# FuenteProto_v11.net
KiCad netlist of a schematic drawn in EAGLE
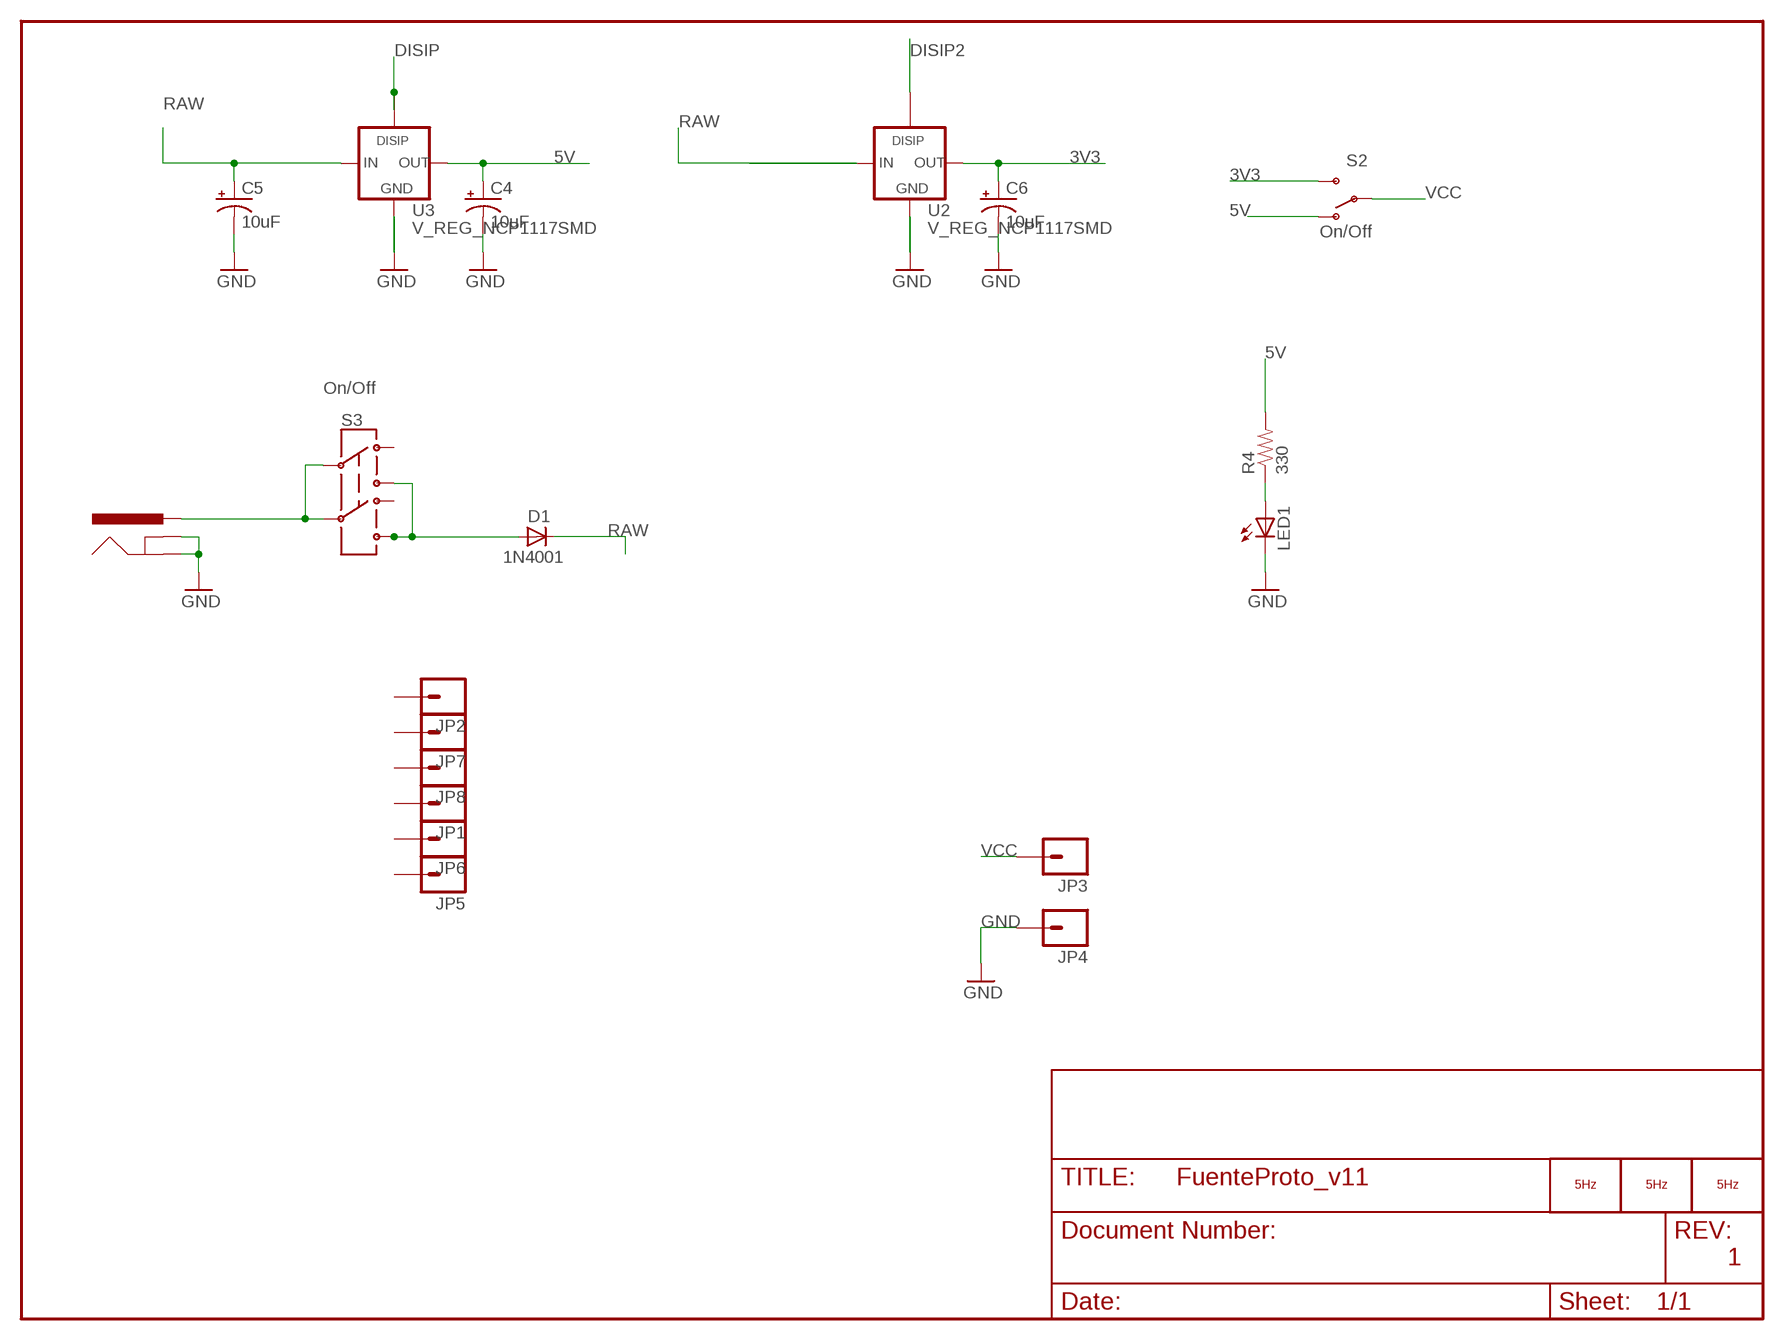
[diagram p0: schematic, sheet 1]

(export (version "E")
  (design (tool "Eeschema 10.0.6"))
  (components
    (comp (ref "C4")
      (value "10uF")
      (footprint "eagle-import:EIA3216")
      (libsource (lib "eagle-import") (part "CAP_POL1206"))
    )
    (comp (ref "C5")
      (value "10uF")
      (footprint "eagle-import:EIA3216")
      (libsource (lib "eagle-import") (part "CAP_POL1206"))
    )
    (comp (ref "C6")
      (value "10uF")
      (footprint "eagle-import:EIA3216")
      (libsource (lib "eagle-import") (part "CAP_POL1206"))
    )
    (comp (ref "D1")
      (value "1N4001")
      (footprint "eagle-import:SMA-DIODE")
      (libsource (lib "eagle-import") (part "DIODESMA"))
    )
    (comp (ref "J1")
      (value "POWER_JACKPTH")
      (footprint "eagle-import:POWER_JACK_PTH")
      (libsource (lib "eagle-import") (part "POWER_JACKPTH"))
    )
    (comp (ref "JP1")
      (value "M01PTH")
      (footprint "eagle-import:1X01")
      (libsource (lib "eagle-import") (part "M01PTH"))
    )
    (comp (ref "JP2")
      (value "M01PTH")
      (footprint "eagle-import:1X01")
      (libsource (lib "eagle-import") (part "M01PTH"))
    )
    (comp (ref "JP3")
      (value "M01PTH")
      (footprint "eagle-import:1X01")
      (libsource (lib "eagle-import") (part "M01PTH"))
    )
    (comp (ref "JP4")
      (value "M01PTH")
      (footprint "eagle-import:1X01")
      (libsource (lib "eagle-import") (part "M01PTH"))
    )
    (comp (ref "JP5")
      (value "M01PTH")
      (footprint "eagle-import:1X01")
      (libsource (lib "eagle-import") (part "M01PTH"))
    )
    (comp (ref "JP6")
      (value "M01PTH")
      (footprint "eagle-import:1X01")
      (libsource (lib "eagle-import") (part "M01PTH"))
    )
    (comp (ref "JP7")
      (value "M01PTH")
      (footprint "eagle-import:1X01")
      (libsource (lib "eagle-import") (part "M01PTH"))
    )
    (comp (ref "JP8")
      (value "M01PTH")
      (footprint "eagle-import:1X01")
      (libsource (lib "eagle-import") (part "M01PTH"))
    )
    (comp (ref "LED1")
      (value "LED0603")
      (footprint "eagle-import:LED-0603")
      (libsource (lib "eagle-import") (part "LED0603"))
    )
    (comp (ref "LOGO1")
      (value "LOGO_5HZ_CIRC_3.5MM")
      (footprint "eagle-import:5HZ_LOGO_CIRC_3.5MM")
      (libsource (lib "eagle-import") (part "LOGO_5HZ_CIRC_3.5MM"))
    )
    (comp (ref "LOGO2")
      (value "LOGO_5HZ_WEB_10MM")
      (footprint "eagle-import:5HZ_WEB_10MM")
      (libsource (lib "eagle-import") (part "LOGO_5HZ_WEB_10MM"))
    )
    (comp (ref "LOGO3")
      (value "LOGO_5HZ_H_10MM")
      (footprint "eagle-import:5HZ_LOGO_H_10MM")
      (libsource (lib "eagle-import") (part "LOGO_5HZ_H_10MM"))
    )
    (comp (ref "R4")
      (value "330")
      (footprint "eagle-import:0603")
      (libsource (lib "eagle-import") (part "RESISTOR0603"))
    )
    (comp (ref "S2")
      (value "On/Off")
      (footprint "eagle-import:AYZ0202")
      (libsource (lib "eagle-import") (part "SWITCH-SPSTSMD"))
    )
    (comp (ref "S3")
      (value "On/Off")
      (footprint "eagle-import:AYZ0202")
      (libsource (lib "eagle-import") (part "AYZ0202"))
    )
    (comp (ref "U2")
      (value "V_REG_NCP1117SMD")
      (footprint "eagle-import:SOT223")
      (libsource (lib "eagle-import") (part "V_REG_NCP1117SMD"))
    )
    (comp (ref "U3")
      (value "V_REG_NCP1117SMD")
      (footprint "eagle-import:SOT223")
      (libsource (lib "eagle-import") (part "V_REG_NCP1117SMD"))
    )
  )
  (nets
    (net (code "1") (name "/3V3") (class "Default")
      (node (ref "C6") (pin "A") (pinfunction "+_A") (pintype "passive"))
      (node (ref "S2") (pin "3") (pinfunction "S_3") (pintype "passive"))
      (node (ref "U2") (pin "2") (pinfunction "OUT_2") (pintype "output"))
    )
    (net (code "2") (name "/5V") (class "Default")
      (node (ref "C4") (pin "A") (pinfunction "+_A") (pintype "passive"))
      (node (ref "R4") (pin "2") (pinfunction "2_2") (pintype "passive"))
      (node (ref "S2") (pin "1") (pinfunction "O_1") (pintype "passive"))
      (node (ref "U3") (pin "2") (pinfunction "OUT_2") (pintype "output"))
    )
    (net (code "3") (name "/DISIP") (class "Default")
      (node (ref "U3") (pin "4") (pinfunction "P$1_4") (pintype "bidirectional"))
    )
    (net (code "4") (name "/DISIP2") (class "Default")
      (node (ref "U2") (pin "4") (pinfunction "P$1_4") (pintype "bidirectional"))
    )
    (net (code "5") (name "/RAW") (class "Default")
      (node (ref "C5") (pin "A") (pinfunction "+_A") (pintype "passive"))
      (node (ref "D1") (pin "C") (pinfunction "C_C") (pintype "passive"))
      (node (ref "U2") (pin "3") (pinfunction "IN_3") (pintype "input"))
      (node (ref "U3") (pin "3") (pinfunction "IN_3") (pintype "input"))
    )
    (net (code "6") (name "/VCC") (class "Default")
      (node (ref "JP3") (pin "1") (pinfunction "1_1") (pintype "passive"))
      (node (ref "S2") (pin "2") (pinfunction "P_2") (pintype "passive"))
    )
    (net (code "7") (name "GND") (class "Default")
      (node (ref "C4") (pin "C") (pinfunction "-_C") (pintype "passive"))
      (node (ref "C5") (pin "C") (pinfunction "-_C") (pintype "passive"))
      (node (ref "C6") (pin "C") (pinfunction "-_C") (pintype "passive"))
      (node (ref "J1") (pin "GND") (pinfunction "GND_GND") (pintype "bidirectional"))
      (node (ref "J1") (pin "GNDBREAK") (pinfunction "GNDBREAK_GNDBREAK") (pintype "bidirectional"))
      (node (ref "JP4") (pin "1") (pinfunction "1_1") (pintype "passive"))
      (node (ref "LED1") (pin "C") (pinfunction "C_C") (pintype "passive"))
      (node (ref "U2") (pin "1") (pinfunction "GND_1") (pintype "input"))
      (node (ref "U3") (pin "1") (pinfunction "GND_1") (pintype "input"))
    )
    (net (code "8") (name "Net-(J1-PadPWR)") (class "Default")
      (node (ref "J1") (pin "PWR") (pinfunction "PWR_PWR") (pintype "bidirectional"))
      (node (ref "S3") (pin "2") (pinfunction "2_2") (pintype "bidirectional"))
      (node (ref "S3") (pin "5") (pinfunction "5_5") (pintype "bidirectional"))
    )
    (net (code "9") (name "Net-(LED1-PadA)") (class "Default")
      (node (ref "LED1") (pin "A") (pinfunction "A_A") (pintype "passive"))
      (node (ref "R4") (pin "1") (pinfunction "1_1") (pintype "passive"))
    )
    (net (code "10") (name "Net-(S3-3)") (class "Default")
      (node (ref "D1") (pin "A") (pinfunction "A_A") (pintype "passive"))
      (node (ref "S3") (pin "1") (pinfunction "3_1") (pintype "bidirectional"))
      (node (ref "S3") (pin "4") (pinfunction "6_4") (pintype "bidirectional"))
    )
    (net (code "11") (name "unconnected-(JP1-Pad1)") (class "Default")
      (node (ref "JP1") (pin "1") (pinfunction "1_1") (pintype "passive"))
    )
    (net (code "12") (name "unconnected-(JP2-Pad1)") (class "Default")
      (node (ref "JP2") (pin "1") (pinfunction "1_1") (pintype "passive"))
    )
    (net (code "13") (name "unconnected-(JP5-Pad1)") (class "Default")
      (node (ref "JP5") (pin "1") (pinfunction "1_1") (pintype "passive"))
    )
    (net (code "14") (name "unconnected-(JP6-Pad1)") (class "Default")
      (node (ref "JP6") (pin "1") (pinfunction "1_1") (pintype "passive"))
    )
    (net (code "15") (name "unconnected-(JP7-Pad1)") (class "Default")
      (node (ref "JP7") (pin "1") (pinfunction "1_1") (pintype "passive"))
    )
    (net (code "16") (name "unconnected-(JP8-Pad1)") (class "Default")
      (node (ref "JP8") (pin "1") (pinfunction "1_1") (pintype "passive"))
    )
    (net (code "17") (name "unconnected-(S3-1-Pad3)") (class "Default")
      (node (ref "S3") (pin "3") (pinfunction "1_3") (pintype "bidirectional"))
    )
    (net (code "18") (name "unconnected-(S3-4-Pad6)") (class "Default")
      (node (ref "S3") (pin "6") (pinfunction "4_6") (pintype "bidirectional"))
    )
  )
)
